# Battery_tester.net
KiCad netlist of a schematic drawn in EAGLE
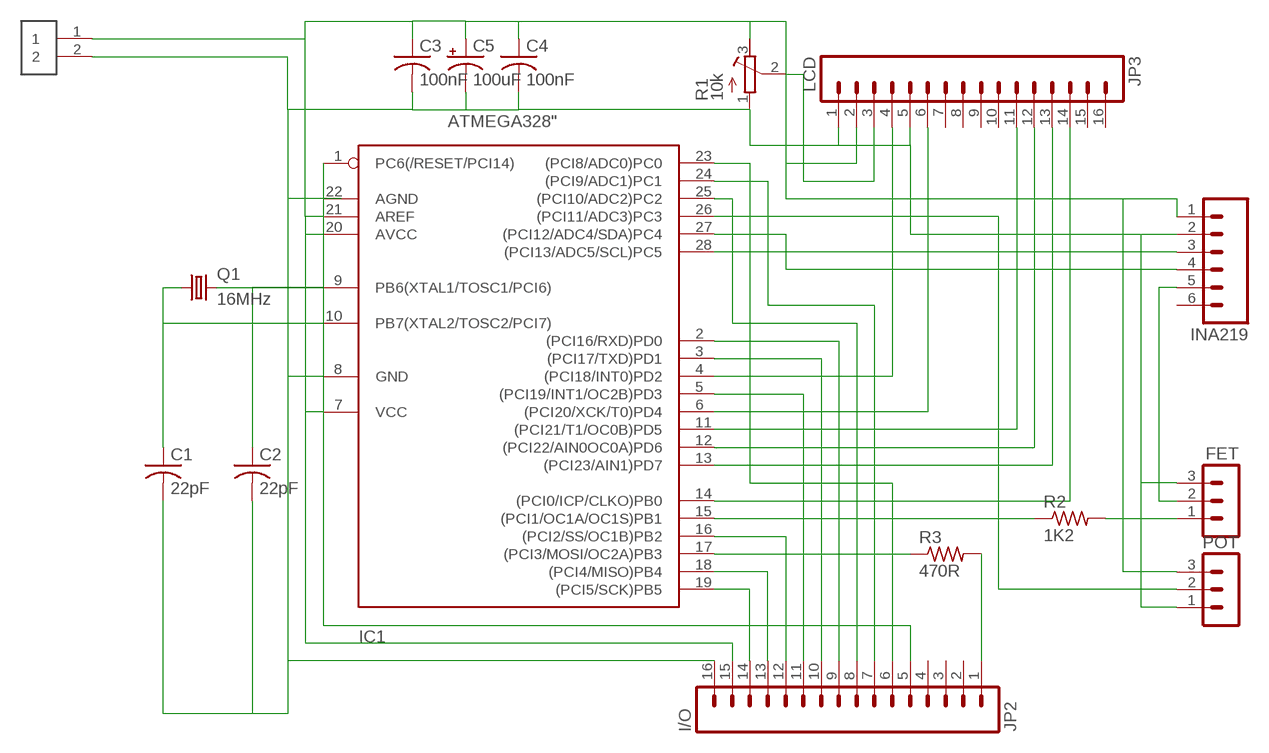
[diagram p0: schematic, sheet 1]

(export (version "E")
  (design (tool "Eeschema 10.0.6"))
  (components
    (comp (ref "C1")
      (value "22pF")
      (footprint "eagle-import:UNPOLARIZED_CAP")
      (libsource (lib "eagle-import") (part "UNPOLARIZED_CAP{dblquote}"))
    )
    (comp (ref "C2")
      (value "22pF")
      (footprint "eagle-import:UNPOLARIZED_CAP")
      (libsource (lib "eagle-import") (part "UNPOLARIZED_CAP{dblquote}"))
    )
    (comp (ref "C3")
      (value "100nF")
      (footprint "eagle-import:UNPOLARIZED_CAP")
      (libsource (lib "eagle-import") (part "UNPOLARIZED_CAP{dblquote}"))
    )
    (comp (ref "C4")
      (value "100nF")
      (footprint "eagle-import:UNPOLARIZED_CAP")
      (libsource (lib "eagle-import") (part "UNPOLARIZED_CAP{dblquote}"))
    )
    (comp (ref "C5")
      (value "100uF")
      (footprint "eagle-import:ELECTROLYTIC_CAP")
      (libsource (lib "eagle-import") (part "ELECTROLYTIC_CAP2.54MM"))
    )
    (comp (ref "FET")
      (value "MA03-1")
      (footprint "eagle-import:MA03-1")
      (libsource (lib "eagle-import") (part "MA03-1"))
    )
    (comp (ref "I/O")
      (value "JP2")
      (footprint "eagle-import:1X16_HEADER")
      (libsource (lib "eagle-import") (part "1X16_HEADER{dblquote}"))
    )
    (comp (ref "IC1")
      (value "ATMEGA328\"")
      (footprint "eagle-import:ATMEGA328")
      (libsource (lib "eagle-import") (part "ATMEGA328{dblquote}"))
    )
    (comp (ref "INA219")
      (value "1X06_HEADER\"")
      (footprint "eagle-import:1X06_HEADER")
      (libsource (lib "eagle-import") (part "1X06_HEADER{dblquote}"))
    )
    (comp (ref "JP3")
      (value "LCD")
      (footprint "eagle-import:1X16_HEADER")
      (libsource (lib "eagle-import") (part "1X16_HEADER{dblquote}"))
    )
    (comp (ref "POT")
      (value "MA03-1")
      (footprint "eagle-import:MA03-1")
      (libsource (lib "eagle-import") (part "MA03-1"))
    )
    (comp (ref "Q1")
      (value "16MHz")
      (footprint "eagle-import:HC18U-V")
      (libsource (lib "eagle-import") (part "CRYSTALHC18U-V"))
    )
    (comp (ref "R1")
      (value "10k")
      (footprint "eagle-import:RTRIM3339P")
      (libsource (lib "eagle-import") (part "R-TRIMM3339P"))
    )
    (comp (ref "R2")
      (value "1K2")
      (footprint "eagle-import:RESISTOR")
      (libsource (lib "eagle-import") (part "RESISTOR1/6WATT"))
    )
    (comp (ref "R3")
      (value "470R")
      (footprint "eagle-import:RESISTOR")
      (libsource (lib "eagle-import") (part "RESISTOR1/6WATT"))
    )
    (comp (ref "USB")
      (value "5V")
      (footprint "eagle-import:1X02_HEADER")
      (libsource (lib "eagle-import") (part "1X02_HEADER"))
    )
  )
  (nets
    (net (code "1") (name "Net-(FET-Pad1)") (class "Default")
      (node (ref "FET") (pin "1") (pinfunction "1_1") (pintype "passive"))
      (node (ref "R2") (pin "2") (pinfunction "2_2") (pintype "passive"))
    )
    (net (code "2") (name "Net-(FET-Pad2)") (class "Default")
      (node (ref "FET") (pin "2") (pinfunction "2_2") (pintype "passive"))
      (node (ref "INA219") (pin "5") (pinfunction "5_5") (pintype "passive"))
    )
    (net (code "3") (name "Net-(I/O-Pad1)") (class "Default")
      (node (ref "I/O") (pin "1") (pinfunction "1_1") (pintype "passive"))
      (node (ref "R3") (pin "2") (pinfunction "2_2") (pintype "passive"))
    )
    (net (code "4") (name "Net-(IC1-(PCI0{slash}ICP{slash}CLKO)PB0)") (class "Default")
      (node (ref "IC1") (pin "14") (pinfunction "(PCI0/ICP/CLKO)PB0_14") (pintype "bidirectional"))
      (node (ref "JP3") (pin "14") (pinfunction "14_14") (pintype "passive"))
    )
    (net (code "5") (name "Net-(IC1-(PCI1{slash}OC1A{slash}OC1S)PB1)") (class "Default")
      (node (ref "IC1") (pin "15") (pinfunction "(PCI1/OC1A/OC1S)PB1_15") (pintype "bidirectional"))
      (node (ref "R2") (pin "1") (pinfunction "1_1") (pintype "passive"))
    )
    (net (code "6") (name "Net-(IC1-(PCI2{slash}SS{slash}OC1B)PB2)") (class "Default")
      (node (ref "I/O") (pin "12") (pinfunction "12_12") (pintype "passive"))
      (node (ref "IC1") (pin "16") (pinfunction "(PCI2/SS/OC1B)PB2_16") (pintype "bidirectional"))
    )
    (net (code "7") (name "Net-(IC1-(PCI3{slash}MOSI{slash}OC2A)PB3)") (class "Default")
      (node (ref "IC1") (pin "17") (pinfunction "(PCI3/MOSI/OC2A)PB3_17") (pintype "bidirectional"))
      (node (ref "R3") (pin "1") (pinfunction "1_1") (pintype "passive"))
    )
    (net (code "8") (name "Net-(IC1-(PCI4{slash}MISO)PB4)") (class "Default")
      (node (ref "I/O") (pin "13") (pinfunction "13_13") (pintype "passive"))
      (node (ref "IC1") (pin "18") (pinfunction "(PCI4/MISO)PB4_18") (pintype "bidirectional"))
    )
    (net (code "9") (name "Net-(IC1-(PCI5{slash}SCK)PB5)") (class "Default")
      (node (ref "I/O") (pin "14") (pinfunction "14_14") (pintype "passive"))
      (node (ref "IC1") (pin "19") (pinfunction "(PCI5/SCK)PB5_19") (pintype "bidirectional"))
    )
    (net (code "10") (name "Net-(IC1-(PCI8{slash}ADC0)PC0)") (class "Default")
      (node (ref "I/O") (pin "6") (pinfunction "6_6") (pintype "passive"))
      (node (ref "IC1") (pin "23") (pinfunction "(PCI8/ADC0)PC0_23") (pintype "bidirectional"))
    )
    (net (code "11") (name "Net-(IC1-(PCI9{slash}ADC1)PC1)") (class "Default")
      (node (ref "I/O") (pin "7") (pinfunction "7_7") (pintype "passive"))
      (node (ref "IC1") (pin "24") (pinfunction "(PCI9/ADC1)PC1_24") (pintype "bidirectional"))
    )
    (net (code "12") (name "Net-(IC1-(PCI10{slash}ADC2)PC2)") (class "Default")
      (node (ref "I/O") (pin "8") (pinfunction "8_8") (pintype "passive"))
      (node (ref "IC1") (pin "25") (pinfunction "(PCI10/ADC2)PC2_25") (pintype "bidirectional"))
    )
    (net (code "13") (name "Net-(IC1-(PCI11{slash}ADC3)PC3)") (class "Default")
      (node (ref "IC1") (pin "26") (pinfunction "(PCI11/ADC3)PC3_26") (pintype "bidirectional"))
      (node (ref "POT") (pin "2") (pinfunction "2_2") (pintype "passive"))
    )
    (net (code "14") (name "Net-(IC1-(PCI12{slash}ADC4{slash}SDA)PC4)") (class "Default")
      (node (ref "IC1") (pin "27") (pinfunction "(PCI12/ADC4/SDA)PC4_27") (pintype "bidirectional"))
      (node (ref "INA219") (pin "4") (pinfunction "4_4") (pintype "passive"))
    )
    (net (code "15") (name "Net-(IC1-(PCI13{slash}ADC5{slash}SCL)PC5)") (class "Default")
      (node (ref "IC1") (pin "28") (pinfunction "(PCI13/ADC5/SCL)PC5_28") (pintype "bidirectional"))
      (node (ref "INA219") (pin "3") (pinfunction "3_3") (pintype "passive"))
    )
    (net (code "16") (name "Net-(IC1-(PCI16{slash}RXD)PD0)") (class "Default")
      (node (ref "I/O") (pin "9") (pinfunction "9_9") (pintype "passive"))
      (node (ref "IC1") (pin "2") (pinfunction "(PCI16/RXD)PD0_2") (pintype "bidirectional"))
    )
    (net (code "17") (name "Net-(IC1-(PCI17{slash}TXD)PD1)") (class "Default")
      (node (ref "I/O") (pin "10") (pinfunction "10_10") (pintype "passive"))
      (node (ref "IC1") (pin "3") (pinfunction "(PCI17/TXD)PD1_3") (pintype "bidirectional"))
    )
    (net (code "18") (name "Net-(IC1-(PCI18{slash}INT0)PD2)") (class "Default")
      (node (ref "IC1") (pin "4") (pinfunction "(PCI18/INT0)PD2_4") (pintype "bidirectional"))
      (node (ref "JP3") (pin "4") (pinfunction "4_4") (pintype "passive"))
    )
    (net (code "19") (name "Net-(IC1-(PCI19{slash}INT1{slash}OC2B)PD3)") (class "Default")
      (node (ref "I/O") (pin "11") (pinfunction "11_11") (pintype "passive"))
      (node (ref "IC1") (pin "5") (pinfunction "(PCI19/INT1/OC2B)PD3_5") (pintype "bidirectional"))
    )
    (net (code "20") (name "Net-(IC1-(PCI20{slash}XCK{slash}T0)PD4)") (class "Default")
      (node (ref "IC1") (pin "6") (pinfunction "(PCI20/XCK/T0)PD4_6") (pintype "bidirectional"))
      (node (ref "JP3") (pin "6") (pinfunction "6_6") (pintype "passive"))
    )
    (net (code "21") (name "Net-(IC1-(PCI21{slash}T1{slash}OC0B)PD5)") (class "Default")
      (node (ref "IC1") (pin "11") (pinfunction "(PCI21/T1/OC0B)PD5_11") (pintype "bidirectional"))
      (node (ref "JP3") (pin "11") (pinfunction "11_11") (pintype "passive"))
    )
    (net (code "22") (name "Net-(IC1-(PCI22{slash}AIN0OC0A)PD6)") (class "Default")
      (node (ref "IC1") (pin "12") (pinfunction "(PCI22/AIN0OC0A)PD6_12") (pintype "bidirectional"))
      (node (ref "JP3") (pin "12") (pinfunction "12_12") (pintype "passive"))
    )
    (net (code "23") (name "Net-(IC1-(PCI23{slash}AIN1)PD7)") (class "Default")
      (node (ref "IC1") (pin "13") (pinfunction "(PCI23/AIN1)PD7_13") (pintype "bidirectional"))
      (node (ref "JP3") (pin "13") (pinfunction "13_13") (pintype "passive"))
    )
    (net (code "24") (name "Net-(IC1-AREF)") (class "Default")
      (node (ref "C3") (pin "1") (pinfunction "1_1") (pintype "passive"))
      (node (ref "C4") (pin "1") (pinfunction "1_1") (pintype "passive"))
      (node (ref "C5") (pin "+") (pinfunction "+_+") (pintype "passive"))
      (node (ref "I/O") (pin "15") (pinfunction "15_15") (pintype "passive"))
      (node (ref "IC1") (pin "20") (pinfunction "AVCC_20") (pintype "bidirectional"))
      (node (ref "IC1") (pin "21") (pinfunction "AREF_21") (pintype "bidirectional"))
      (node (ref "IC1") (pin "7") (pinfunction "VCC_7") (pintype "bidirectional"))
      (node (ref "INA219") (pin "1") (pinfunction "1_1") (pintype "passive"))
      (node (ref "JP3") (pin "2") (pinfunction "2_2") (pintype "passive"))
      (node (ref "POT") (pin "3") (pinfunction "3_3") (pintype "passive"))
      (node (ref "R1") (pin "3") (pinfunction "A_3") (pintype "passive"))
      (node (ref "USB") (pin "1") (pinfunction "1_1") (pintype "bidirectional"))
    )
    (net (code "25") (name "Net-(IC1-GND)") (class "Default")
      (node (ref "C1") (pin "2") (pinfunction "2_2") (pintype "passive"))
      (node (ref "C2") (pin "2") (pinfunction "2_2") (pintype "passive"))
      (node (ref "C3") (pin "2") (pinfunction "2_2") (pintype "passive"))
      (node (ref "C4") (pin "2") (pinfunction "2_2") (pintype "passive"))
      (node (ref "C5") (pin "-") (pinfunction "-_-") (pintype "passive"))
      (node (ref "FET") (pin "3") (pinfunction "3_3") (pintype "passive"))
      (node (ref "I/O") (pin "16") (pinfunction "16_16") (pintype "passive"))
      (node (ref "IC1") (pin "8") (pinfunction "GND_8") (pintype "bidirectional"))
      (node (ref "INA219") (pin "2") (pinfunction "2_2") (pintype "passive"))
      (node (ref "JP3") (pin "1") (pinfunction "1_1") (pintype "passive"))
      (node (ref "JP3") (pin "5") (pinfunction "5_5") (pintype "passive"))
      (node (ref "POT") (pin "1") (pinfunction "1_1") (pintype "passive"))
      (node (ref "R1") (pin "1") (pinfunction "E_1") (pintype "passive"))
      (node (ref "USB") (pin "2") (pinfunction "2_2") (pintype "bidirectional"))
    )
    (net (code "26") (name "Net-(IC1-PB6(XTAL1{slash}TOSC1{slash}PCI6))") (class "Default")
      (node (ref "C2") (pin "1") (pinfunction "1_1") (pintype "passive"))
      (node (ref "IC1") (pin "9") (pinfunction "PB6(XTAL1/TOSC1/PCI6)_9") (pintype "bidirectional"))
      (node (ref "Q1") (pin "2") (pinfunction "2_2") (pintype "passive"))
    )
    (net (code "27") (name "Net-(IC1-PB7(XTAL2{slash}TOSC2{slash}PCI7))") (class "Default")
      (node (ref "C1") (pin "1") (pinfunction "1_1") (pintype "passive"))
      (node (ref "IC1") (pin "10") (pinfunction "PB7(XTAL2/TOSC2/PCI7)_10") (pintype "bidirectional"))
      (node (ref "Q1") (pin "1") (pinfunction "1_1") (pintype "passive"))
    )
    (net (code "28") (name "Net-(IC1-PC6({slash}RESET{slash}PCI14))") (class "Default")
      (node (ref "I/O") (pin "5") (pinfunction "5_5") (pintype "passive"))
      (node (ref "IC1") (pin "1") (pinfunction "PC6(/RESET/PCI14)_1") (pintype "bidirectional"))
    )
    (net (code "29") (name "Net-(R1-S)") (class "Default")
      (node (ref "JP3") (pin "3") (pinfunction "3_3") (pintype "passive"))
      (node (ref "R1") (pin "2") (pinfunction "S_2") (pintype "passive"))
    )
    (net (code "30") (name "unconnected-(I/O-Pad2)") (class "Default")
      (node (ref "I/O") (pin "2") (pinfunction "2_2") (pintype "passive"))
    )
    (net (code "31") (name "unconnected-(I/O-Pad3)") (class "Default")
      (node (ref "I/O") (pin "3") (pinfunction "3_3") (pintype "passive"))
    )
    (net (code "32") (name "unconnected-(I/O-Pad4)") (class "Default")
      (node (ref "I/O") (pin "4") (pinfunction "4_4") (pintype "passive"))
    )
    (net (code "33") (name "unconnected-(IC1-AGND-Pad22)") (class "Default")
      (node (ref "IC1") (pin "22") (pinfunction "AGND_22") (pintype "bidirectional"))
    )
    (net (code "34") (name "unconnected-(INA219-Pad6)") (class "Default")
      (node (ref "INA219") (pin "6") (pinfunction "6_6") (pintype "passive"))
    )
    (net (code "35") (name "unconnected-(JP3-Pad7)") (class "Default")
      (node (ref "JP3") (pin "7") (pinfunction "7_7") (pintype "passive"))
    )
    (net (code "36") (name "unconnected-(JP3-Pad8)") (class "Default")
      (node (ref "JP3") (pin "8") (pinfunction "8_8") (pintype "passive"))
    )
    (net (code "37") (name "unconnected-(JP3-Pad9)") (class "Default")
      (node (ref "JP3") (pin "9") (pinfunction "9_9") (pintype "passive"))
    )
    (net (code "38") (name "unconnected-(JP3-Pad10)") (class "Default")
      (node (ref "JP3") (pin "10") (pinfunction "10_10") (pintype "passive"))
    )
    (net (code "39") (name "unconnected-(JP3-Pad15)") (class "Default")
      (node (ref "JP3") (pin "15") (pinfunction "15_15") (pintype "passive"))
    )
    (net (code "40") (name "unconnected-(JP3-Pad16)") (class "Default")
      (node (ref "JP3") (pin "16") (pinfunction "16_16") (pintype "passive"))
    )
  )
)
